# e-stop.net
KiCad netlist of a schematic drawn in Altium Designer
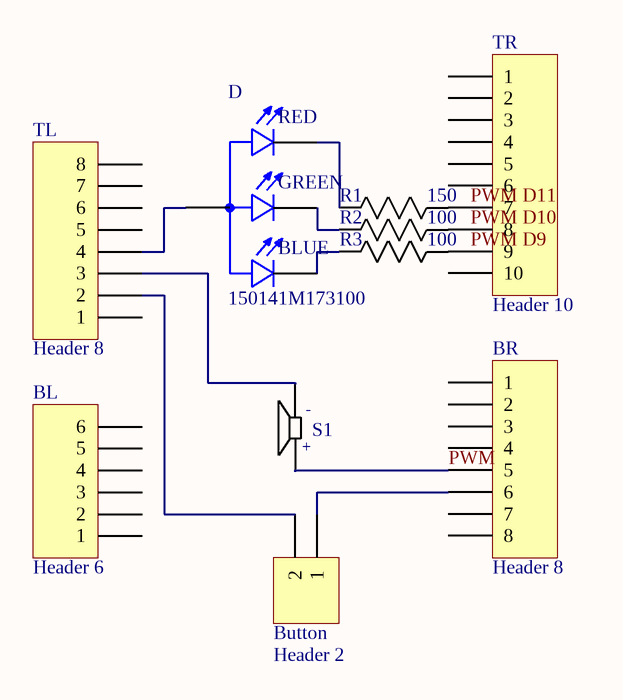
[diagram p0: e-stop.SchDoc]

(export (version "E")
  (design (tool "Eeschema 10.0.6"))
  (components
    (comp (ref "BL")
      (value "Header 6")
      (footprint "HDR1X6")
      (description "Header, 6-Pin")
      (fields (field (name "PUBLISHER") "Altium Limited"))
      (libsource (lib "Miscellaneous Connectors") (part "Header 6"))
    )
    (comp (ref "BR")
      (value "Header 8")
      (footprint "HDR1X8")
      (description "Header, 8-Pin")
      (fields (field (name "PUBLISHER") "Altium Limited"))
      (libsource (lib "Miscellaneous Connectors") (part "Header 8"))
    )
    (comp (ref "Button")
      (value "Header 2")
      (footprint "HDR1X2")
      (description "Header, 2-Pin")
      (fields (field (name "PUBLISHER") "Altium Limited"))
      (libsource (lib "Miscellaneous Connectors") (part "Header 2"))
    )
    (comp (ref "D")
      (value "150141M173100")
      (footprint "LED_150141M173100")
      (fields (field (name "MF") "Wurth Electronics"))
      (libsource (lib "150141M173100") (part "150141M173100"))
    )
    (comp (ref "R1")
      (value "150")
      (footprint "0805")
      (description "RES SMD 150 OHM 5% 1/8W 0805")
      (fields (field (name "TOLERANCE") "5%"))
      (libsource (lib "AltiumLibraries") (part "RES 150.0 1/8W"))
    )
    (comp (ref "R2")
      (value "100")
      (footprint "0805")
      (description "RES SMD 100 OHM 5% 1/8W 0805")
      (fields (field (name "TOLERANCE") "5%"))
      (libsource (lib "AltiumLibraries") (part "RES 100.0 1/8W"))
    )
    (comp (ref "R3")
      (value "100")
      (footprint "0805")
      (description "RES SMD 100 OHM 5% 1/8W 0805")
      (fields (field (name "TOLERANCE") "5%"))
      (libsource (lib "") (part "RES 100.0 1/8W_1"))
    )
    (comp (ref "S1")
      (value "BUZZER CEM-1203")
      (footprint "CEM-1203")
      (description "AUDIO MAGNETIC XDCR 3-5V TH")
      (libsource (lib "AltiumLibraries") (part "BUZZER CEM-1203"))
    )
    (comp (ref "TL")
      (value "Header 8")
      (footprint "HDR1X8")
      (description "Header, 8-Pin")
      (fields (field (name "PUBLISHER") "Altium Limited"))
      (libsource (lib "") (part "Header 8_1"))
    )
    (comp (ref "TR")
      (value "Header 10")
      (footprint "HDR1X10")
      (description "Header, 10-Pin")
      (fields (field (name "PUBLISHER") "Altium Limited"))
      (libsource (lib "Miscellaneous Connectors") (part "Header 10"))
    )
  )
  (nets
    (net (code "1") (name "/PWM") (class "Default")
      (node (ref "BR") (pin "5") (pinfunction "5_5") (pintype "passive"))
      (node (ref "S1") (pin "P") (pinfunction "P_P") (pintype "passive"))
    )
    (net (code "5") (name "Net-(BR-Pad6)") (class "Default")
      (node (ref "BR") (pin "6") (pinfunction "6_6") (pintype "passive"))
      (node (ref "Button") (pin "1") (pinfunction "1_1") (pintype "passive"))
    )
    (net (code "6") (name "Net-(Button-Pad2)") (class "Default")
      (node (ref "Button") (pin "2") (pinfunction "2_2") (pintype "passive"))
      (node (ref "TL") (pin "2") (pinfunction "2_2") (pintype "passive"))
    )
    (net (code "7") (name "Net-(D-A)") (class "Default")
      (node (ref "D") (pin "1") (pinfunction "A_1") (pintype "passive"))
      (node (ref "TL") (pin "4") (pinfunction "4_4") (pintype "passive"))
    )
    (net (code "8") (name "Net-(D-B_C)") (class "Default")
      (node (ref "D") (pin "2") (pinfunction "B_C_2") (pintype "passive"))
      (node (ref "R3") (pin "2") (pinfunction "R2_2") (pintype "passive"))
    )
    (net (code "9") (name "Net-(D-G_C)") (class "Default")
      (node (ref "D") (pin "4") (pinfunction "G_C_4") (pintype "passive"))
      (node (ref "R2") (pin "2") (pinfunction "R2_2") (pintype "passive"))
    )
    (net (code "10") (name "Net-(D-R_C)") (class "Default")
      (node (ref "D") (pin "3") (pinfunction "R_C_3") (pintype "passive"))
      (node (ref "R1") (pin "2") (pinfunction "R2_2") (pintype "passive"))
    )
    (net (code "11") (name "Net-(R1-R1)") (class "Default")
      (node (ref "R1") (pin "1") (pinfunction "R1_1") (pintype "passive"))
      (node (ref "TR") (pin "7") (pinfunction "7_7") (pintype "passive"))
    )
    (net (code "12") (name "Net-(R2-R1)") (class "Default")
      (node (ref "R2") (pin "1") (pinfunction "R1_1") (pintype "passive"))
      (node (ref "TR") (pin "8") (pinfunction "8_8") (pintype "passive"))
    )
    (net (code "13") (name "Net-(R3-R1)") (class "Default")
      (node (ref "R3") (pin "1") (pinfunction "R1_1") (pintype "passive"))
      (node (ref "TR") (pin "9") (pinfunction "9_9") (pintype "passive"))
    )
    (net (code "14") (name "Net-(S1-PadN)") (class "Default")
      (node (ref "S1") (pin "N") (pinfunction "N_N") (pintype "passive"))
      (node (ref "TL") (pin "3") (pinfunction "3_3") (pintype "passive"))
    )
    (net (code "15") (name "unconnected-(BL-Pad1)") (class "Default")
      (node (ref "BL") (pin "1") (pinfunction "1_1") (pintype "passive"))
    )
    (net (code "16") (name "unconnected-(BL-Pad2)") (class "Default")
      (node (ref "BL") (pin "2") (pinfunction "2_2") (pintype "passive"))
    )
    (net (code "17") (name "unconnected-(BL-Pad3)") (class "Default")
      (node (ref "BL") (pin "3") (pinfunction "3_3") (pintype "passive"))
    )
    (net (code "18") (name "unconnected-(BL-Pad4)") (class "Default")
      (node (ref "BL") (pin "4") (pinfunction "4_4") (pintype "passive"))
    )
    (net (code "19") (name "unconnected-(BL-Pad5)") (class "Default")
      (node (ref "BL") (pin "5") (pinfunction "5_5") (pintype "passive"))
    )
    (net (code "20") (name "unconnected-(BL-Pad6)") (class "Default")
      (node (ref "BL") (pin "6") (pinfunction "6_6") (pintype "passive"))
    )
    (net (code "21") (name "unconnected-(BR-Pad1)") (class "Default")
      (node (ref "BR") (pin "1") (pinfunction "1_1") (pintype "passive"))
    )
    (net (code "22") (name "unconnected-(BR-Pad2)") (class "Default")
      (node (ref "BR") (pin "2") (pinfunction "2_2") (pintype "passive"))
    )
    (net (code "23") (name "unconnected-(BR-Pad3)") (class "Default")
      (node (ref "BR") (pin "3") (pinfunction "3_3") (pintype "passive"))
    )
    (net (code "24") (name "unconnected-(BR-Pad4)") (class "Default")
      (node (ref "BR") (pin "4") (pinfunction "4_4") (pintype "passive"))
    )
    (net (code "25") (name "unconnected-(BR-Pad7)") (class "Default")
      (node (ref "BR") (pin "7") (pinfunction "7_7") (pintype "passive"))
    )
    (net (code "26") (name "unconnected-(BR-Pad8)") (class "Default")
      (node (ref "BR") (pin "8") (pinfunction "8_8") (pintype "passive"))
    )
    (net (code "27") (name "unconnected-(TL-Pad1)") (class "Default")
      (node (ref "TL") (pin "1") (pinfunction "1_1") (pintype "passive"))
    )
    (net (code "28") (name "unconnected-(TL-Pad5)") (class "Default")
      (node (ref "TL") (pin "5") (pinfunction "5_5") (pintype "passive"))
    )
    (net (code "29") (name "unconnected-(TL-Pad6)") (class "Default")
      (node (ref "TL") (pin "6") (pinfunction "6_6") (pintype "passive"))
    )
    (net (code "30") (name "unconnected-(TL-Pad7)") (class "Default")
      (node (ref "TL") (pin "7") (pinfunction "7_7") (pintype "passive"))
    )
    (net (code "31") (name "unconnected-(TL-Pad8)") (class "Default")
      (node (ref "TL") (pin "8") (pinfunction "8_8") (pintype "passive"))
    )
    (net (code "32") (name "unconnected-(TR-Pad1)") (class "Default")
      (node (ref "TR") (pin "1") (pinfunction "1_1") (pintype "passive"))
    )
    (net (code "33") (name "unconnected-(TR-Pad2)") (class "Default")
      (node (ref "TR") (pin "2") (pinfunction "2_2") (pintype "passive"))
    )
    (net (code "34") (name "unconnected-(TR-Pad3)") (class "Default")
      (node (ref "TR") (pin "3") (pinfunction "3_3") (pintype "passive"))
    )
    (net (code "35") (name "unconnected-(TR-Pad4)") (class "Default")
      (node (ref "TR") (pin "4") (pinfunction "4_4") (pintype "passive"))
    )
    (net (code "36") (name "unconnected-(TR-Pad5)") (class "Default")
      (node (ref "TR") (pin "5") (pinfunction "5_5") (pintype "passive"))
    )
    (net (code "37") (name "unconnected-(TR-Pad6)") (class "Default")
      (node (ref "TR") (pin "6") (pinfunction "6_6") (pintype "passive"))
    )
    (net (code "38") (name "unconnected-(TR-Pad10)") (class "Default")
      (node (ref "TR") (pin "10") (pinfunction "10_10") (pintype "passive"))
    )
  )
)
